# 3_3V_Regulator.net
KiCad netlist of a schematic drawn in Altium Designer
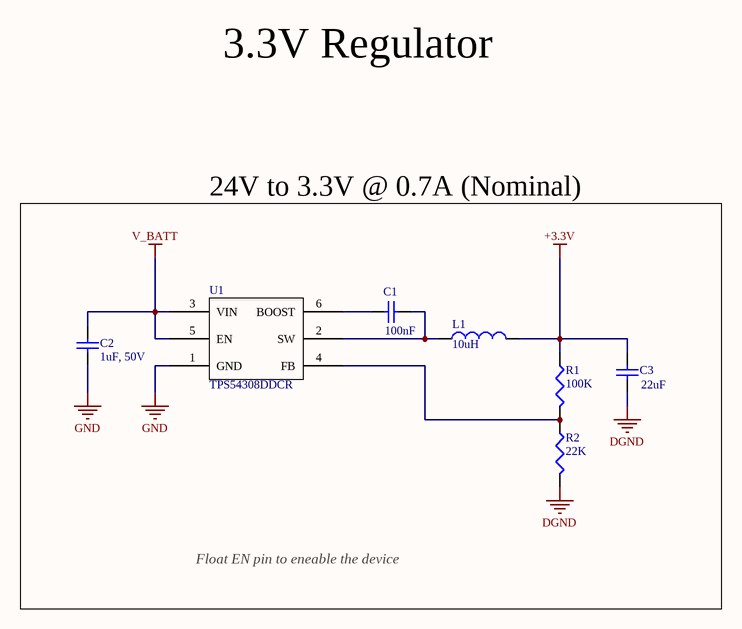
[diagram p0: 3.3V Regulator.SchDoc]

(export (version "E")
  (design (tool "Eeschema 10.0.6"))
  (components
    (comp (ref "C1")
      (value "100nF")
      (footprint "CAPC2012X06N")
      (description "Capacitor")
      (fields (field (name "Comment") "Cap") (field (name "PUBLISHER") "Altium Limited"))
      (libsource (lib "Miscellaneous Devices") (part "Cap"))
    )
    (comp (ref "C2")
      (value "1uF, 50V")
      (footprint "CAPC2012X06N")
      (description "Capacitor")
      (fields (field (name "Comment") "Cap") (field (name "PUBLISHER") "Altium Limited"))
      (libsource (lib "Miscellaneous Devices") (part "Cap"))
    )
    (comp (ref "C3")
      (value "22uF")
      (footprint "CAPC2012X06N")
      (description "Capacitor")
      (fields (field (name "Comment") "Cap") (field (name "PUBLISHER") "Altium Limited"))
      (libsource (lib "Miscellaneous Devices") (part "Cap"))
    )
    (comp (ref "L1")
      (value "10uH")
      (footprint "INDC8063X52N")
      (fields (field (name "Comment") "Inductor") (field (name "PUBLISHER") "Altium Limited"))
      (libsource (lib "Miscellaneous Devices") (part "Inductor"))
    )
    (comp (ref "R1")
      (value "100K")
      (footprint "RES 0603 MEDIUM")
      (description "Resistor")
      (fields (field (name "Comment") "Res3") (field (name "PUBLISHER") "Altium Limited"))
      (libsource (lib "Miscellaneous Devices") (part "Res3"))
    )
    (comp (ref "R2")
      (value "22K")
      (footprint "RES 0603 MEDIUM")
      (description "Resistor")
      (fields (field (name "Comment") "Res3") (field (name "PUBLISHER") "Altium Limited"))
      (libsource (lib "Miscellaneous Devices") (part "Res3"))
    )
    (comp (ref "U1")
      (value "TPS54308DDCR")
      (footprint "SOT95P280X110-6N")
      (description "Buck Switching Regulator IC Positive Adjustable 1V 1 Output 3A SOT-23-6 Thin, TSOT-23-6")
      (libsource (lib "MOSFET Board Schematic Library") (part "TPS54308DDCR"))
    )
  )
  (nets
    (net (code "1") (name "+3.3V") (class "Default")
      (node (ref "C3") (pin "2") (pinfunction "2_2") (pintype "passive"))
      (node (ref "L1") (pin "2") (pinfunction "2_2") (pintype "passive"))
      (node (ref "R1") (pin "1") (pinfunction "1_1") (pintype "passive"))
    )
    (net (code "2") (name "DGND") (class "Default")
      (node (ref "C3") (pin "1") (pinfunction "1_1") (pintype "passive"))
      (node (ref "R2") (pin "2") (pinfunction "2_2") (pintype "passive"))
    )
    (net (code "3") (name "GND") (class "Default")
      (node (ref "C2") (pin "1") (pinfunction "1_1") (pintype "passive"))
      (node (ref "U1") (pin "1") (pinfunction "GND_1") (pintype "passive"))
    )
    (net (code "4") (name "Net-(U1-BOOST)") (class "Default")
      (node (ref "C1") (pin "1") (pinfunction "1_1") (pintype "passive"))
      (node (ref "U1") (pin "6") (pinfunction "BOOST_6") (pintype "passive"))
    )
    (net (code "5") (name "Net-(U1-FB)") (class "Default")
      (node (ref "R1") (pin "2") (pinfunction "2_2") (pintype "passive"))
      (node (ref "R2") (pin "1") (pinfunction "1_1") (pintype "passive"))
      (node (ref "U1") (pin "4") (pinfunction "FB_4") (pintype "passive"))
    )
    (net (code "6") (name "Net-(U1-SW)") (class "Default")
      (node (ref "C1") (pin "2") (pinfunction "2_2") (pintype "passive"))
      (node (ref "L1") (pin "1") (pinfunction "1_1") (pintype "passive"))
      (node (ref "U1") (pin "2") (pinfunction "SW_2") (pintype "passive"))
    )
    (net (code "7") (name "V_BATT") (class "Default")
      (node (ref "C2") (pin "2") (pinfunction "2_2") (pintype "passive"))
      (node (ref "U1") (pin "3") (pinfunction "VIN_3") (pintype "passive"))
      (node (ref "U1") (pin "5") (pinfunction "EN_5") (pintype "passive"))
    )
  )
)
